# 11_HEATER.net
KiCad netlist of a schematic drawn in Altium Designer
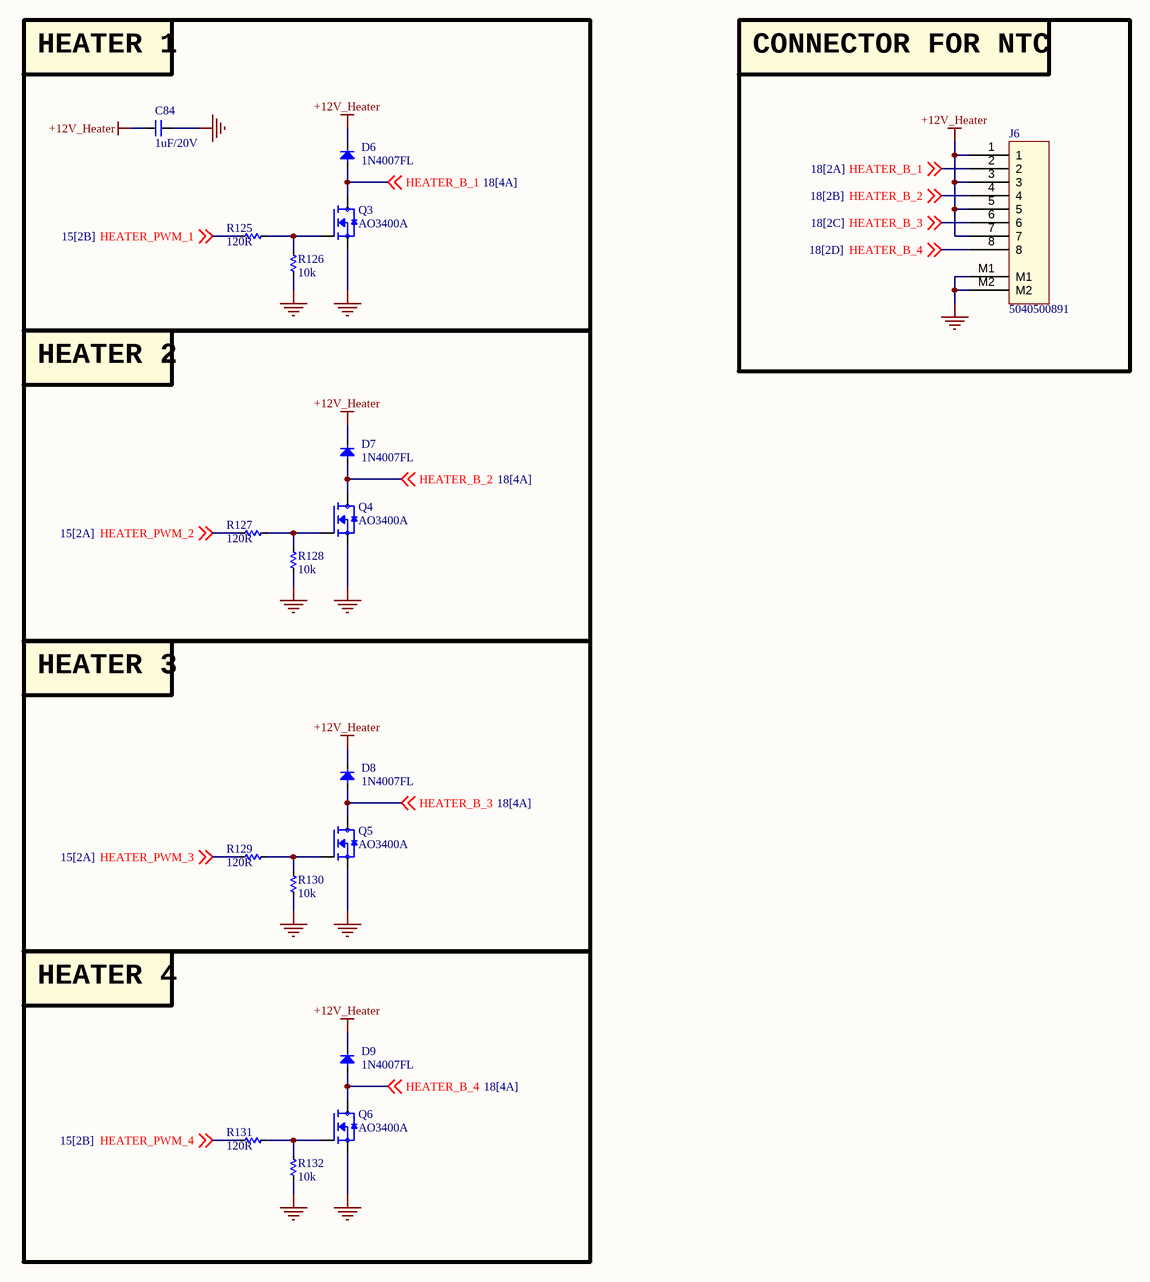
[diagram p0: 11_HEATER.SchDoc]

(export (version "E")
  (design (tool "Eeschema 10.0.6"))
  (components
    (comp (ref "C84")
      (value "1uF/20V")
      (footprint "CAP_C_1005X60")
      (description "CAP CHIP")
      (libsource (lib "LABLIB") (part "_CAP_C_2"))
    )
    (comp (ref "D6")
      (value "1N4007FL")
      (footprint "SOD3717X145N")
      (description "Default Diode")
      (fields (field (name "PUBLISHER") "Altium Limited"))
      (libsource (lib "LABLIB") (part "Diode SMD"))
    )
    (comp (ref "D7")
      (value "1N4007FL")
      (footprint "SOD3717X145N")
      (description "Default Diode")
      (fields (field (name "PUBLISHER") "Altium Limited"))
      (libsource (lib "LABLIB") (part "Diode SMD"))
    )
    (comp (ref "D8")
      (value "1N4007FL")
      (footprint "SOD3717X145N")
      (description "Default Diode")
      (fields (field (name "PUBLISHER") "Altium Limited"))
      (libsource (lib "LABLIB") (part "Diode SMD"))
    )
    (comp (ref "D9")
      (value "1N4007FL")
      (footprint "SOD3717X145N")
      (description "Default Diode")
      (fields (field (name "PUBLISHER") "Altium Limited"))
      (libsource (lib "LABLIB") (part "Diode SMD"))
    )
    (comp (ref "J6")
      (value "5040500891")
      (footprint "MOLEX_5040500891")
      (libsource (lib "LABLIB") (part "Header 8x1_2M"))
    )
    (comp (ref "Q3")
      (value "AO3400A")
      (footprint "SOT95P240X120-3N")
      (description "N-Channel 30 V 5.7A (Ta) 1.4W (Ta) Surface Mount SOT-23-3")
      (fields (field (name "MF") "Alpha & Omega Semiconductor"))
      (libsource (lib "new_component") (part "MOSFET_N"))
    )
    (comp (ref "Q4")
      (value "AO3400A")
      (footprint "SOT95P240X120-3N")
      (description "N-Channel 30 V 5.7A (Ta) 1.4W (Ta) Surface Mount SOT-23-3")
      (fields (field (name "MF") "Alpha & Omega Semiconductor"))
      (libsource (lib "new_component") (part "MOSFET_N"))
    )
    (comp (ref "Q5")
      (value "AO3400A")
      (footprint "SOT95P240X120-3N")
      (description "N-Channel 30 V 5.7A (Ta) 1.4W (Ta) Surface Mount SOT-23-3")
      (fields (field (name "MF") "Alpha & Omega Semiconductor"))
      (libsource (lib "new_component") (part "MOSFET_N"))
    )
    (comp (ref "Q6")
      (value "AO3400A")
      (footprint "SOT95P240X120-3N")
      (description "N-Channel 30 V 5.7A (Ta) 1.4W (Ta) Surface Mount SOT-23-3")
      (fields (field (name "MF") "Alpha & Omega Semiconductor"))
      (libsource (lib "new_component") (part "MOSFET_N"))
    )
    (comp (ref "R125")
      (value "120R")
      (footprint "RES_C_1005X40")
      (description "RES")
      (libsource (lib "LABLIB") (part "_RES_B_2"))
    )
    (comp (ref "R126")
      (value "10k")
      (footprint "RES_C_1005X40")
      (description "RES")
      (libsource (lib "LABLIB") (part "_RES_B_2"))
    )
    (comp (ref "R127")
      (value "120R")
      (footprint "RES_C_1005X40")
      (description "RES")
      (libsource (lib "LABLIB") (part "_RES_B_2"))
    )
    (comp (ref "R128")
      (value "10k")
      (footprint "RES_C_1005X40")
      (description "RES")
      (libsource (lib "LABLIB") (part "_RES_B_2"))
    )
    (comp (ref "R129")
      (value "120R")
      (footprint "RES_C_1005X40")
      (description "RES")
      (libsource (lib "LABLIB") (part "_RES_B_2"))
    )
    (comp (ref "R130")
      (value "10k")
      (footprint "RES_C_1005X40")
      (description "RES")
      (libsource (lib "LABLIB") (part "_RES_B_2"))
    )
    (comp (ref "R131")
      (value "120R")
      (footprint "RES_C_1005X40")
      (description "RES")
      (libsource (lib "LABLIB") (part "_RES_B_2"))
    )
    (comp (ref "R132")
      (value "10k")
      (footprint "RES_C_1005X40")
      (description "RES")
      (libsource (lib "LABLIB") (part "_RES_B_2"))
    )
  )
  (nets
    (net (code "1") (name "+12V_Heater") (class "Default")
      (node (ref "C84") (pin "2") (pinfunction "2_2") (pintype "passive"))
      (node (ref "D6") (pin "1") (pinfunction "K_1") (pintype "passive"))
      (node (ref "D7") (pin "1") (pinfunction "K_1") (pintype "passive"))
      (node (ref "D8") (pin "1") (pinfunction "K_1") (pintype "passive"))
      (node (ref "D9") (pin "1") (pinfunction "K_1") (pintype "passive"))
      (node (ref "J6") (pin "1") (pinfunction "1_1") (pintype "passive"))
      (node (ref "J6") (pin "3") (pinfunction "3_3") (pintype "passive"))
      (node (ref "J6") (pin "5") (pinfunction "5_5") (pintype "passive"))
      (node (ref "J6") (pin "7") (pinfunction "7_7") (pintype "passive"))
    )
    (net (code "2") (name "GND") (class "Default")
      (node (ref "C84") (pin "1") (pinfunction "1_1") (pintype "passive"))
      (node (ref "J6") (pin "M1") (pinfunction "M1_M1") (pintype "passive"))
      (node (ref "J6") (pin "M2") (pinfunction "M2_M2") (pintype "passive"))
      (node (ref "Q3") (pin "2") (pinfunction "S_2") (pintype "passive"))
      (node (ref "Q4") (pin "2") (pinfunction "S_2") (pintype "passive"))
      (node (ref "Q5") (pin "2") (pinfunction "S_2") (pintype "passive"))
      (node (ref "Q6") (pin "2") (pinfunction "S_2") (pintype "passive"))
      (node (ref "R126") (pin "1") (pinfunction "1_1") (pintype "passive"))
      (node (ref "R128") (pin "1") (pinfunction "1_1") (pintype "passive"))
      (node (ref "R130") (pin "1") (pinfunction "1_1") (pintype "passive"))
      (node (ref "R132") (pin "1") (pinfunction "1_1") (pintype "passive"))
    )
    (net (code "3") (name "HEATER_B_1") (class "Default")
      (node (ref "D6") (pin "2") (pinfunction "A_2") (pintype "passive"))
      (node (ref "J6") (pin "2") (pinfunction "2_2") (pintype "passive"))
      (node (ref "Q3") (pin "3") (pinfunction "D_3") (pintype "passive"))
    )
    (net (code "4") (name "HEATER_B_2") (class "Default")
      (node (ref "D7") (pin "2") (pinfunction "A_2") (pintype "passive"))
      (node (ref "J6") (pin "4") (pinfunction "4_4") (pintype "passive"))
      (node (ref "Q4") (pin "3") (pinfunction "D_3") (pintype "passive"))
    )
    (net (code "5") (name "HEATER_B_3") (class "Default")
      (node (ref "D8") (pin "2") (pinfunction "A_2") (pintype "passive"))
      (node (ref "J6") (pin "6") (pinfunction "6_6") (pintype "passive"))
      (node (ref "Q5") (pin "3") (pinfunction "D_3") (pintype "passive"))
    )
    (net (code "6") (name "HEATER_B_4") (class "Default")
      (node (ref "D9") (pin "2") (pinfunction "A_2") (pintype "passive"))
      (node (ref "J6") (pin "8") (pinfunction "8_8") (pintype "passive"))
      (node (ref "Q6") (pin "3") (pinfunction "D_3") (pintype "passive"))
    )
    (net (code "7") (name "HEATER_PWM_1") (class "Default")
      (node (ref "R125") (pin "1") (pinfunction "1_1") (pintype "passive"))
    )
    (net (code "8") (name "HEATER_PWM_2") (class "Default")
      (node (ref "R127") (pin "1") (pinfunction "1_1") (pintype "passive"))
    )
    (net (code "9") (name "HEATER_PWM_3") (class "Default")
      (node (ref "R129") (pin "1") (pinfunction "1_1") (pintype "passive"))
    )
    (net (code "10") (name "HEATER_PWM_4") (class "Default")
      (node (ref "R131") (pin "1") (pinfunction "1_1") (pintype "passive"))
    )
    (net (code "11") (name "Net-(Q3-G)") (class "Default")
      (node (ref "Q3") (pin "1") (pinfunction "G_1") (pintype "passive"))
      (node (ref "R125") (pin "2") (pinfunction "2_2") (pintype "passive"))
      (node (ref "R126") (pin "2") (pinfunction "2_2") (pintype "passive"))
    )
    (net (code "12") (name "Net-(Q4-G)") (class "Default")
      (node (ref "Q4") (pin "1") (pinfunction "G_1") (pintype "passive"))
      (node (ref "R127") (pin "2") (pinfunction "2_2") (pintype "passive"))
      (node (ref "R128") (pin "2") (pinfunction "2_2") (pintype "passive"))
    )
    (net (code "13") (name "Net-(Q5-G)") (class "Default")
      (node (ref "Q5") (pin "1") (pinfunction "G_1") (pintype "passive"))
      (node (ref "R129") (pin "2") (pinfunction "2_2") (pintype "passive"))
      (node (ref "R130") (pin "2") (pinfunction "2_2") (pintype "passive"))
    )
    (net (code "14") (name "Net-(Q6-G)") (class "Default")
      (node (ref "Q6") (pin "1") (pinfunction "G_1") (pintype "passive"))
      (node (ref "R131") (pin "2") (pinfunction "2_2") (pintype "passive"))
      (node (ref "R132") (pin "2") (pinfunction "2_2") (pintype "passive"))
    )
  )
)
